# CAN1.net
KiCad netlist of a schematic drawn in Altium Designer
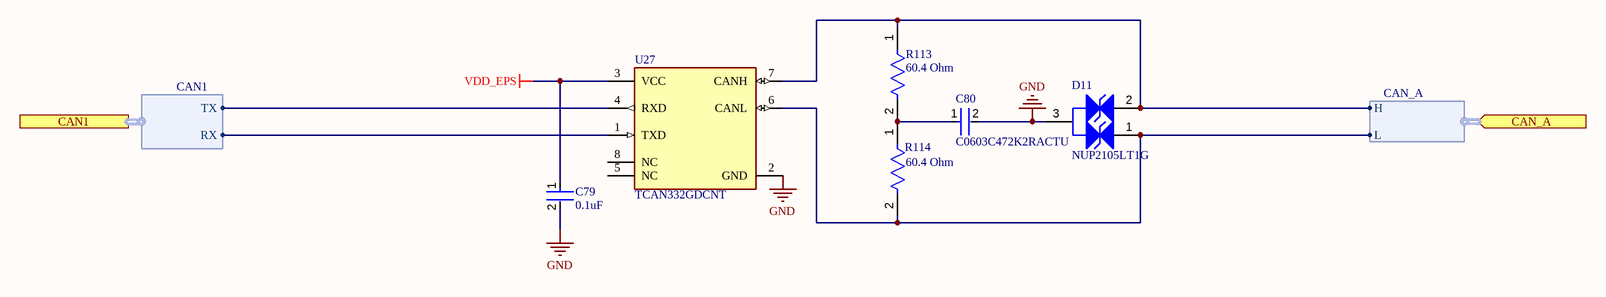
[diagram p0: CAN1.SchDoc]

(export (version "E")
  (design (tool "Eeschema 10.0.6"))
  (components
    (comp (ref "C79")
      (value "0.1uF")
      (footprint "FP-C0603C-CF-MFG")
      (description "CAP CER 0.1UF 50V X7R 0603")
      (fields (field (name "TOLERANCE") "0.1") (field (name "MANUFACTURER") "KEMET"))
      (libsource (lib "Altium Content Vault") (part "b4654b650e69147ec39a6b967a45e02"))
    )
    (comp (ref "C80")
      (value "C0603C472K2RACTU")
      (footprint "FP-C0603C-CF-MFG")
      (description "CAP CER 4700PF 200V 10% X7R 0603")
      (fields
        (field (name "OCTOPART") "https://octopart.com/c0603c472k2ractu-kemet-17058096")
        (field (name "MANUFACTURER") "KEMET")
      )
      (libsource (lib "Altium Content Vault") (part "b4654b650e69147ec39a6b967a45e02"))
    )
    (comp (ref "D11")
      (value "NUP2105LT1G")
      (footprint "ONSC-SOT-23-3-318-08_V")
      (description "Dual Line CAN Bus Protector, 3-Pin SOT-23, Pb-Free, Tape and Reel")
      (fields (field (name "MANUFACTURER") "On Semiconductor"))
      (libsource (lib "Altium Content Vault") (part "ONSC-NUP21X5X-SOT-23-3-318-08"))
    )
    (comp (ref "R113")
      (value "60.4 Ohm")
      (footprint "FP-RC1608-IPC_C")
      (description "Res Thick Film 0603 60.4Ω 1% 0.1W ±100ppm/°C Molded SMD T/R")
      (fields (field (name "TOLERANCE") "1%"))
      (libsource (lib "Altium Content Vault") (part "1029c3af85768c4190bb7ad29bc67b5"))
    )
    (comp (ref "R114")
      (value "60.4 Ohm")
      (footprint "FP-RC1608-IPC_C")
      (description "Res Thick Film 0603 60.4Ω 1% 0.1W ±100ppm/°C Molded SMD T/R")
      (fields (field (name "TOLERANCE") "1%"))
      (libsource (lib "Altium Content Vault") (part "1029c3af85768c4190bb7ad29bc67b5"))
    )
    (comp (ref "U27")
      (value "TCAN332GDCNT")
      (footprint "FP-DCN0008A-IPC_C")
      (description "IC TRANSCEIVER 1/1 SOT23-8")
      (libsource (lib "Altium Content Vault") (part "f57d81afad401941ce556981ca48666"))
    )
  )
  (nets
    (net (code "3") (name "/H") (class "Default")
      (node (ref "D11") (pin "2") (pinfunction "K_2") (pintype "passive"))
      (node (ref "R113") (pin "1") (pinfunction "1_1") (pintype "passive"))
      (node (ref "U27") (pin "7") (pinfunction "CANH_7") (pintype "bidirectional"))
    )
    (net (code "4") (name "/L") (class "Default")
      (node (ref "D11") (pin "1") (pinfunction "K_1") (pintype "passive"))
      (node (ref "R114") (pin "2") (pinfunction "2_2") (pintype "passive"))
      (node (ref "U27") (pin "6") (pinfunction "CANL_6") (pintype "bidirectional"))
    )
    (net (code "5") (name "/RX") (class "Default")
      (node (ref "U27") (pin "1") (pinfunction "TXD_1") (pintype "input"))
    )
    (net (code "6") (name "/TX") (class "Default")
      (node (ref "U27") (pin "4") (pinfunction "RXD_4") (pintype "output"))
    )
    (net (code "9") (name "GND") (class "Default")
      (node (ref "C79") (pin "2") (pinfunction "2_2") (pintype "passive"))
      (node (ref "C80") (pin "2") (pinfunction "2_2") (pintype "passive"))
      (node (ref "D11") (pin "3") (pinfunction "K_3") (pintype "passive"))
      (node (ref "U27") (pin "2") (pinfunction "GND_2") (pintype "power_in"))
    )
    (net (code "10") (name "Net-(C80-Pad1)") (class "Default")
      (node (ref "C80") (pin "1") (pinfunction "1_1") (pintype "passive"))
      (node (ref "R113") (pin "2") (pinfunction "2_2") (pintype "passive"))
      (node (ref "R114") (pin "1") (pinfunction "1_1") (pintype "passive"))
    )
    (net (code "11") (name "VDD_EPS") (class "Default")
      (node (ref "C79") (pin "1") (pinfunction "1_1") (pintype "passive"))
      (node (ref "U27") (pin "3") (pinfunction "VCC_3") (pintype "power_in"))
    )
    (net (code "12") (name "unconnected-(U27-NC-Pad5)") (class "Default")
      (node (ref "U27") (pin "5") (pinfunction "NC_5") (pintype "passive"))
    )
    (net (code "13") (name "unconnected-(U27-NC-Pad8)") (class "Default")
      (node (ref "U27") (pin "8") (pinfunction "NC_8") (pintype "passive"))
    )
  )
)
